# PDR.net
KiCad netlist of a schematic drawn in EAGLE
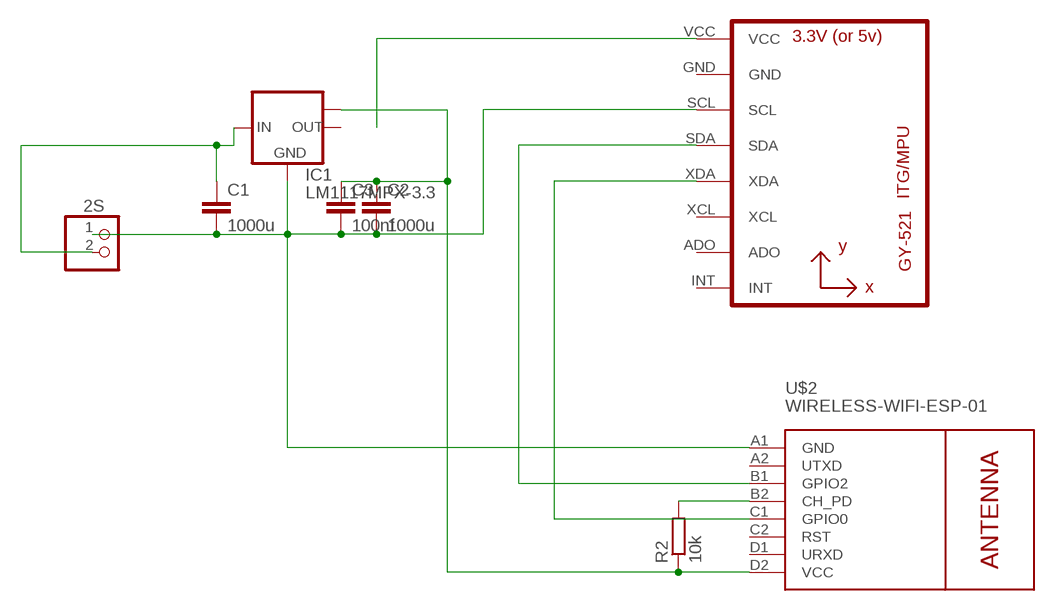
[diagram p0: schematic, sheet 1]

(export (version "E")
  (design (tool "Eeschema 10.0.6"))
  (components
    (comp (ref "2S")
      (value "PINHD-1X2")
      (footprint "eagle-import:1X02")
      (libsource (lib "eagle-import") (part "PINHD-1X2"))
    )
    (comp (ref "C1")
      (value "1000u")
      (footprint "eagle-import:C2.5-2")
      (libsource (lib "eagle-import") (part "C2.5/2"))
    )
    (comp (ref "C2")
      (value "1000u")
      (footprint "eagle-import:C2.5-2")
      (libsource (lib "eagle-import") (part "C2.5/2"))
    )
    (comp (ref "C3")
      (value "100nf")
      (footprint "eagle-import:C2.5-2")
      (libsource (lib "eagle-import") (part "C2.5/2"))
    )
    (comp (ref "GY-91")
      (value "GY-521MPU6050")
      (footprint "eagle-import:GY-521")
      (libsource (lib "eagle-import") (part "GY-521MPU6050"))
    )
    (comp (ref "IC1")
      (value "LM1117MPX-3.3")
      (footprint "eagle-import:SOT223")
      (libsource (lib "eagle-import") (part "LM1117MPX-3.3"))
    )
    (comp (ref "R2")
      (value "10k")
      (footprint "eagle-import:0204_7")
      (libsource (lib "eagle-import") (part "R-EU_0204/7"))
    )
    (comp (ref "U$2")
      (value "WIRELESS-WIFI-ESP-01")
      (footprint "eagle-import:WIRELESS-WIFI-ESP-01")
      (libsource (lib "eagle-import") (part "WIRELESS-WIFI-ESP-01"))
    )
  )
  (nets
    (net (code "1") (name "Net-(IC1-GND)") (class "Default")
      (node (ref "2S") (pin "1") (pinfunction "1_1") (pintype "passive"))
      (node (ref "C1") (pin "2") (pinfunction "2_2") (pintype "passive"))
      (node (ref "C2") (pin "2") (pinfunction "2_2") (pintype "passive"))
      (node (ref "C3") (pin "2") (pinfunction "2_2") (pintype "passive"))
      (node (ref "GY-91") (pin "SCL") (pinfunction "SCL_SCL") (pintype "bidirectional"))
      (node (ref "IC1") (pin "1") (pinfunction "GND_1") (pintype "input"))
      (node (ref "U$2") (pin "A1") (pinfunction "GND_A1") (pintype "power_in"))
    )
    (net (code "2") (name "Net-(IC1-IN)") (class "Default")
      (node (ref "2S") (pin "2") (pinfunction "2_2") (pintype "passive"))
      (node (ref "C1") (pin "1") (pinfunction "1_1") (pintype "passive"))
      (node (ref "IC1") (pin "3") (pinfunction "IN_3") (pintype "input"))
    )
    (net (code "3") (name "Net-(IC1-OUT1)") (class "Default")
      (node (ref "C2") (pin "1") (pinfunction "1_1") (pintype "passive"))
      (node (ref "C3") (pin "1") (pinfunction "1_1") (pintype "passive"))
      (node (ref "IC1") (pin "TAB") (pinfunction "OUT1_TAB") (pintype "passive"))
      (node (ref "R2") (pin "1") (pinfunction "1_1") (pintype "passive"))
      (node (ref "U$2") (pin "D2") (pinfunction "VCC_D2") (pintype "power_in"))
    )
    (net (code "4") (name "Net-(U$2-CH_PD)") (class "Default")
      (node (ref "R2") (pin "2") (pinfunction "2_2") (pintype "passive"))
      (node (ref "U$2") (pin "B2") (pinfunction "CH_PD_B2") (pintype "bidirectional"))
    )
    (net (code "5") (name "Net-(U$2-GPIO0)") (class "Default")
      (node (ref "GY-91") (pin "XDA") (pinfunction "XDA_XDA") (pintype "bidirectional"))
      (node (ref "U$2") (pin "C1") (pinfunction "GPIO0_C1") (pintype "bidirectional"))
    )
    (net (code "6") (name "Net-(U$2-GPIO2)") (class "Default")
      (node (ref "GY-91") (pin "SDA") (pinfunction "SDA_SDA") (pintype "bidirectional"))
      (node (ref "U$2") (pin "B1") (pinfunction "GPIO2_B1") (pintype "bidirectional"))
    )
    (net (code "7") (name "unconnected-(GY-91-PadADO)") (class "Default")
      (node (ref "GY-91") (pin "ADO") (pinfunction "ADO_ADO") (pintype "bidirectional"))
    )
    (net (code "8") (name "unconnected-(GY-91-PadGND)") (class "Default")
      (node (ref "GY-91") (pin "GND") (pinfunction "GND_GND") (pintype "bidirectional"))
    )
    (net (code "9") (name "unconnected-(GY-91-PadINT)") (class "Default")
      (node (ref "GY-91") (pin "INT") (pinfunction "INT_INT") (pintype "bidirectional"))
    )
    (net (code "10") (name "unconnected-(GY-91-PadVCC)") (class "Default")
      (node (ref "GY-91") (pin "VCC") (pinfunction "VCC_VCC") (pintype "bidirectional"))
    )
    (net (code "11") (name "unconnected-(GY-91-PadXCL)") (class "Default")
      (node (ref "GY-91") (pin "XCL") (pinfunction "XCL_XCL") (pintype "bidirectional"))
    )
    (net (code "12") (name "unconnected-(IC1-OUT-Pad2)") (class "Default")
      (node (ref "IC1") (pin "2") (pinfunction "OUT_2") (pintype "passive"))
    )
    (net (code "13") (name "unconnected-(U$2-RST-PadC2)") (class "Default")
      (node (ref "U$2") (pin "C2") (pinfunction "RST_C2") (pintype "bidirectional"))
    )
    (net (code "14") (name "unconnected-(U$2-URXD-PadD1)") (class "Default")
      (node (ref "U$2") (pin "D1") (pinfunction "URXD_D1") (pintype "bidirectional"))
    )
    (net (code "15") (name "unconnected-(U$2-UTXD-PadA2)") (class "Default")
      (node (ref "U$2") (pin "A2") (pinfunction "UTXD_A2") (pintype "bidirectional"))
    )
  )
)
